# AP_board.net
KiCad netlist of a schematic drawn in EAGLE
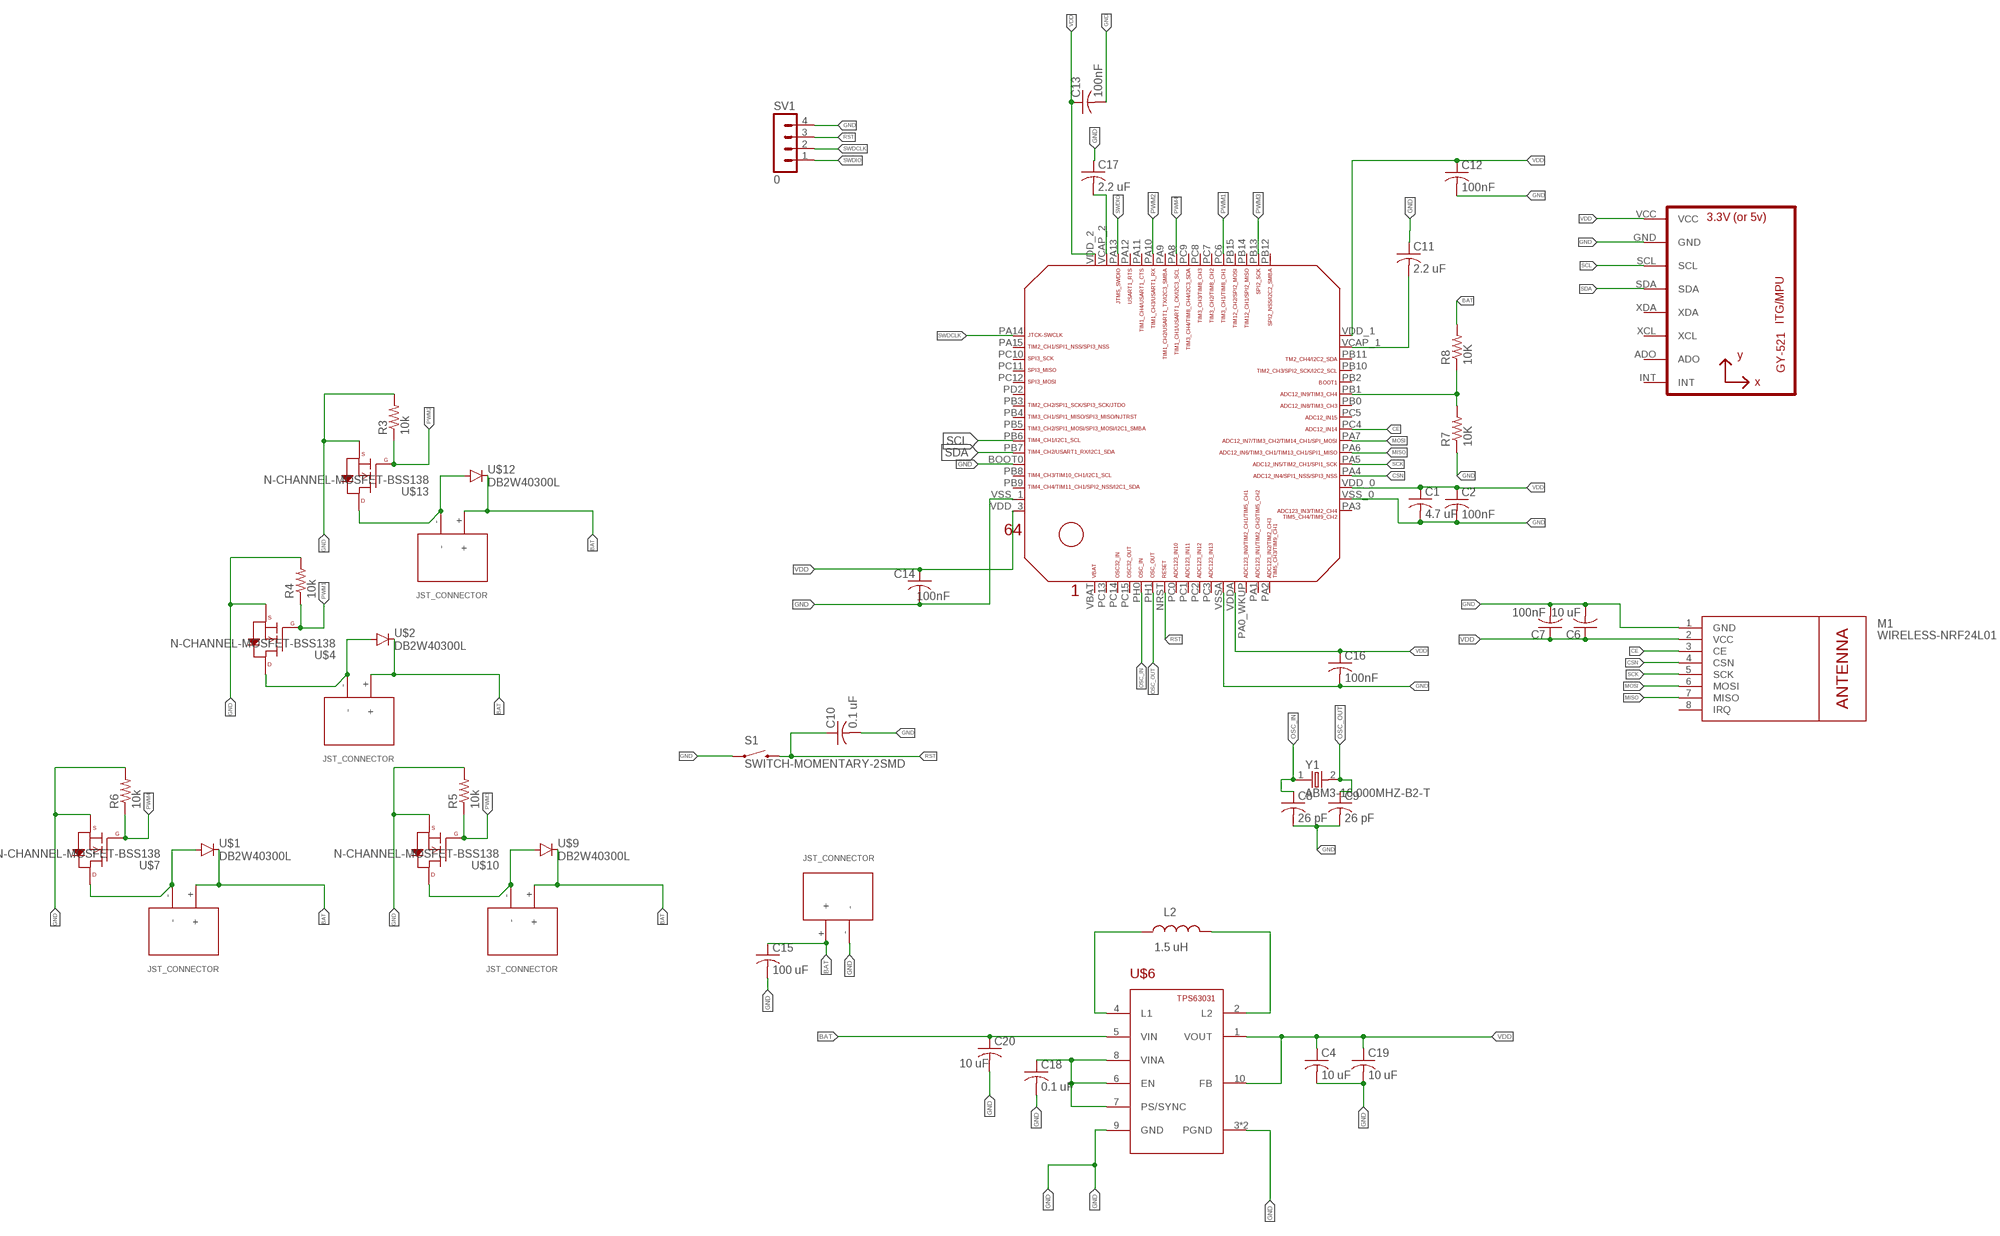
[diagram p0: schematic, sheet 1]

(export (version "E")
  (design (tool "Eeschema 10.0.6"))
  (components
    (comp (ref "C1")
      (value "4.7 uF")
      (footprint "eagle-import:C0603")
      (libsource (lib "eagle-import") (part "C-USC0603"))
    )
    (comp (ref "C2")
      (value "100nF")
      (footprint "eagle-import:C0603")
      (libsource (lib "eagle-import") (part "C-USC0603"))
    )
    (comp (ref "C4")
      (value "10 uF")
      (footprint "eagle-import:C0603")
      (libsource (lib "eagle-import") (part "C-USC0603"))
    )
    (comp (ref "C6")
      (value "10 uF")
      (footprint "eagle-import:C0603")
      (libsource (lib "eagle-import") (part "C-USC0603"))
    )
    (comp (ref "C7")
      (value "100nF")
      (footprint "eagle-import:C0603")
      (libsource (lib "eagle-import") (part "C-USC0603"))
    )
    (comp (ref "C8")
      (value "26 pF")
      (footprint "eagle-import:C0603")
      (libsource (lib "eagle-import") (part "C-USC0603"))
    )
    (comp (ref "C9")
      (value "26 pF")
      (footprint "eagle-import:C0603")
      (libsource (lib "eagle-import") (part "C-USC0603"))
    )
    (comp (ref "C10")
      (value "0.1 uF")
      (footprint "eagle-import:C0603")
      (libsource (lib "eagle-import") (part "C-USC0603"))
    )
    (comp (ref "C11")
      (value "2.2 uF")
      (footprint "eagle-import:C0603")
      (libsource (lib "eagle-import") (part "C-USC0603"))
    )
    (comp (ref "C12")
      (value "100nF")
      (footprint "eagle-import:C0603")
      (libsource (lib "eagle-import") (part "C-USC0603"))
    )
    (comp (ref "C13")
      (value "100nF")
      (footprint "eagle-import:C0603")
      (libsource (lib "eagle-import") (part "C-USC0603"))
    )
    (comp (ref "C14")
      (value "100nF")
      (footprint "eagle-import:C0603")
      (libsource (lib "eagle-import") (part "C-USC0603"))
    )
    (comp (ref "C15")
      (value "100 uF")
      (footprint "eagle-import:C1206")
      (libsource (lib "eagle-import") (part "C-USC1206"))
    )
    (comp (ref "C16")
      (value "100nF")
      (footprint "eagle-import:C0603")
      (libsource (lib "eagle-import") (part "C-USC0603"))
    )
    (comp (ref "C17")
      (value "2.2 uF")
      (footprint "eagle-import:C0603")
      (libsource (lib "eagle-import") (part "C-USC0603"))
    )
    (comp (ref "C18")
      (value "0.1 uF")
      (footprint "eagle-import:C0603")
      (libsource (lib "eagle-import") (part "C-USC0603"))
    )
    (comp (ref "C19")
      (value "10 uF")
      (footprint "eagle-import:C0603")
      (libsource (lib "eagle-import") (part "C-USC0603"))
    )
    (comp (ref "C20")
      (value "10 uF")
      (footprint "eagle-import:C0603")
      (libsource (lib "eagle-import") (part "C-USC0603"))
    )
    (comp (ref "L2")
      (value "1.5 uH")
      (footprint "eagle-import:IND1212")
      (libsource (lib "eagle-import") (part "INDUCTOR"))
    )
    (comp (ref "M1")
      (value "WIRELESS-NRF24L01")
      (footprint "eagle-import:WIRELESS-NRF24L01")
      (libsource (lib "eagle-import") (part "WIRELESS-NRF24L01"))
    )
    (comp (ref "R3")
      (value "10k")
      (footprint "eagle-import:R0603")
      (libsource (lib "eagle-import") (part "R-US_R0603"))
    )
    (comp (ref "R4")
      (value "10k")
      (footprint "eagle-import:R0603")
      (libsource (lib "eagle-import") (part "R-US_R0603"))
    )
    (comp (ref "R5")
      (value "10k")
      (footprint "eagle-import:R0603")
      (libsource (lib "eagle-import") (part "R-US_R0603"))
    )
    (comp (ref "R6")
      (value "10k")
      (footprint "eagle-import:R0603")
      (libsource (lib "eagle-import") (part "R-US_R0603"))
    )
    (comp (ref "R7")
      (value "10K")
      (footprint "eagle-import:R0603")
      (libsource (lib "eagle-import") (part "R-US_R0603"))
    )
    (comp (ref "R8")
      (value "10K")
      (footprint "eagle-import:R0603")
      (libsource (lib "eagle-import") (part "R-US_R0603"))
    )
    (comp (ref "S1")
      (value "SWITCH-MOMENTARY-2SMD")
      (footprint "eagle-import:TACTILE-SWITCH-SMD")
      (libsource (lib "eagle-import") (part "SWITCH-MOMENTARY-2SMD"))
    )
    (comp (ref "SV1")
      (value "0")
      (footprint "eagle-import:MA04-1")
      (libsource (lib "eagle-import") (part "MA04-1"))
    )
    (comp (ref "U$1")
      (value "DB2W40300L")
      (footprint "eagle-import:MINI2-F3-B")
      (libsource (lib "eagle-import") (part "DB2W40300L"))
    )
    (comp (ref "U$2")
      (value "DB2W40300L")
      (footprint "eagle-import:MINI2-F3-B")
      (libsource (lib "eagle-import") (part "DB2W40300L"))
    )
    (comp (ref "U$3")
      (value "STM32F405/415_LQFP64")
      (footprint "eagle-import:STM32F405_415_LQFP64")
      (libsource (lib "eagle-import") (part "STM32F405/415_LQFP64"))
    )
    (comp (ref "U$4")
      (value "N-CHANNEL-MOSFET-BSS138")
      (footprint "eagle-import:SOT23-3")
      (libsource (lib "eagle-import") (part "N-CHANNEL-MOSFET-BSS138"))
    )
    (comp (ref "U$5")
      (value "JST_CONNECTOR_FEMALE")
      (footprint "eagle-import:JST_CONNECTOR_FEMALE")
      (libsource (lib "eagle-import") (part "JST_CONNECTOR_FEMALE"))
    )
    (comp (ref "U$6")
      (value "TPS63031")
      (footprint "eagle-import:SON-10")
      (libsource (lib "eagle-import") (part "TPS63031"))
    )
    (comp (ref "U$7")
      (value "N-CHANNEL-MOSFET-BSS138")
      (footprint "eagle-import:SOT23-3")
      (libsource (lib "eagle-import") (part "N-CHANNEL-MOSFET-BSS138"))
    )
    (comp (ref "U$8")
      (value "JST_CONNECTOR_FEMALE")
      (footprint "eagle-import:JST_CONNECTOR_FEMALE")
      (libsource (lib "eagle-import") (part "JST_CONNECTOR_FEMALE"))
    )
    (comp (ref "U$9")
      (value "DB2W40300L")
      (footprint "eagle-import:MINI2-F3-B")
      (libsource (lib "eagle-import") (part "DB2W40300L"))
    )
    (comp (ref "U$10")
      (value "N-CHANNEL-MOSFET-BSS138")
      (footprint "eagle-import:SOT23-3")
      (libsource (lib "eagle-import") (part "N-CHANNEL-MOSFET-BSS138"))
    )
    (comp (ref "U$11")
      (value "JST_CONNECTOR_FEMALE")
      (footprint "eagle-import:JST_CONNECTOR_FEMALE")
      (libsource (lib "eagle-import") (part "JST_CONNECTOR_FEMALE"))
    )
    (comp (ref "U$12")
      (value "DB2W40300L")
      (footprint "eagle-import:MINI2-F3-B")
      (libsource (lib "eagle-import") (part "DB2W40300L"))
    )
    (comp (ref "U$13")
      (value "N-CHANNEL-MOSFET-BSS138")
      (footprint "eagle-import:SOT23-3")
      (libsource (lib "eagle-import") (part "N-CHANNEL-MOSFET-BSS138"))
    )
    (comp (ref "U$14")
      (value "JST_CONNECTOR_FEMALE")
      (footprint "eagle-import:JST_CONNECTOR_FEMALE")
      (libsource (lib "eagle-import") (part "JST_CONNECTOR_FEMALE"))
    )
    (comp (ref "U$17")
      (value "JST_CONNECTOR_FEMALE")
      (footprint "eagle-import:JST_CONNECTOR_FEMALE")
      (libsource (lib "eagle-import") (part "JST_CONNECTOR_FEMALE"))
    )
    (comp (ref "U1")
      (value "GY-521MPU6050")
      (footprint "eagle-import:GY-521")
      (libsource (lib "eagle-import") (part "GY-521MPU6050"))
    )
    (comp (ref "Y1")
      (value "ABM3-16.000MHZ-B2-T")
      (footprint "eagle-import:XTAL500X320X130N")
      (fields (field (name "DIGI-KEY_PART_NUMBER") "535-9103-1-ND") (field (name "MF") "Abracon"))
      (libsource (lib "eagle-import") (part "ABM3-16.000MHZ-B2-T"))
    )
  )
  (nets
    (net (code "1") (name "BAT") (class "Default")
      (node (ref "C15") (pin "1") (pinfunction "1_1") (pintype "passive"))
      (node (ref "C20") (pin "1") (pinfunction "1_1") (pintype "passive"))
      (node (ref "R8") (pin "2") (pinfunction "2_2") (pintype "passive"))
      (node (ref "U$1") (pin "NEG") (pinfunction "GPIN_NEG") (pintype "passive"))
      (node (ref "U$11") (pin "+") (pinfunction "+_+") (pintype "bidirectional"))
      (node (ref "U$12") (pin "NEG") (pinfunction "GPIN_NEG") (pintype "passive"))
      (node (ref "U$14") (pin "+") (pinfunction "+_+") (pintype "bidirectional"))
      (node (ref "U$17") (pin "+") (pinfunction "+_+") (pintype "bidirectional"))
      (node (ref "U$2") (pin "NEG") (pinfunction "GPIN_NEG") (pintype "passive"))
      (node (ref "U$5") (pin "+") (pinfunction "+_+") (pintype "bidirectional"))
      (node (ref "U$6") (pin "5") (pinfunction "VIN_5") (pintype "bidirectional"))
      (node (ref "U$8") (pin "+") (pinfunction "+_+") (pintype "bidirectional"))
      (node (ref "U$9") (pin "NEG") (pinfunction "GPIN_NEG") (pintype "passive"))
    )
    (net (code "2") (name "CE") (class "Default")
      (node (ref "M1") (pin "3") (pinfunction "CE_3") (pintype "bidirectional"))
      (node (ref "U$3") (pin "PC4") (pinfunction "PC4_PC4") (pintype "bidirectional"))
    )
    (net (code "3") (name "CSN") (class "Default")
      (node (ref "M1") (pin "4") (pinfunction "CSN_4") (pintype "bidirectional"))
      (node (ref "U$3") (pin "PA4") (pinfunction "PA4_PA4") (pintype "bidirectional"))
    )
    (net (code "4") (name "GND") (class "Default")
      (node (ref "C1") (pin "2") (pinfunction "2_2") (pintype "passive"))
      (node (ref "C10") (pin "2") (pinfunction "2_2") (pintype "passive"))
      (node (ref "C11") (pin "1") (pinfunction "1_1") (pintype "passive"))
      (node (ref "C12") (pin "2") (pinfunction "2_2") (pintype "passive"))
      (node (ref "C13") (pin "2") (pinfunction "2_2") (pintype "passive"))
      (node (ref "C14") (pin "2") (pinfunction "2_2") (pintype "passive"))
      (node (ref "C15") (pin "2") (pinfunction "2_2") (pintype "passive"))
      (node (ref "C16") (pin "2") (pinfunction "2_2") (pintype "passive"))
      (node (ref "C17") (pin "1") (pinfunction "1_1") (pintype "passive"))
      (node (ref "C18") (pin "2") (pinfunction "2_2") (pintype "passive"))
      (node (ref "C19") (pin "2") (pinfunction "2_2") (pintype "passive"))
      (node (ref "C2") (pin "2") (pinfunction "2_2") (pintype "passive"))
      (node (ref "C20") (pin "2") (pinfunction "2_2") (pintype "passive"))
      (node (ref "C4") (pin "2") (pinfunction "2_2") (pintype "passive"))
      (node (ref "C6") (pin "2") (pinfunction "2_2") (pintype "passive"))
      (node (ref "C7") (pin "2") (pinfunction "2_2") (pintype "passive"))
      (node (ref "C8") (pin "2") (pinfunction "2_2") (pintype "passive"))
      (node (ref "C9") (pin "2") (pinfunction "2_2") (pintype "passive"))
      (node (ref "M1") (pin "1") (pinfunction "GND_1") (pintype "power_in"))
      (node (ref "R3") (pin "2") (pinfunction "2_2") (pintype "passive"))
      (node (ref "R4") (pin "2") (pinfunction "2_2") (pintype "passive"))
      (node (ref "R5") (pin "2") (pinfunction "2_2") (pintype "passive"))
      (node (ref "R6") (pin "2") (pinfunction "2_2") (pintype "passive"))
      (node (ref "R7") (pin "1") (pinfunction "1_1") (pintype "passive"))
      (node (ref "S1") (pin "1") (pinfunction "1_1") (pintype "passive"))
      (node (ref "SV1") (pin "4") (pinfunction "4_4") (pintype "passive"))
      (node (ref "U$10") (pin "2") (pinfunction "S_2") (pintype "passive"))
      (node (ref "U$13") (pin "2") (pinfunction "S_2") (pintype "passive"))
      (node (ref "U$17") (pin "-") (pinfunction "-_-") (pintype "bidirectional"))
      (node (ref "U$3") (pin "BOOT0") (pinfunction "BOOT0_BOOT0") (pintype "bidirectional"))
      (node (ref "U$3") (pin "VSSA") (pinfunction "VSSA_VSSA") (pintype "bidirectional"))
      (node (ref "U$3") (pin "VSS_0") (pinfunction "VSS_0_VSS_0") (pintype "bidirectional"))
      (node (ref "U$3") (pin "VSS_1") (pinfunction "VSS_1_VSS_1") (pintype "bidirectional"))
      (node (ref "U$4") (pin "2") (pinfunction "S_2") (pintype "passive"))
      (node (ref "U$6") (pin "3") (pinfunction "PGND_3") (pintype "bidirectional"))
      (node (ref "U$6") (pin "9") (pinfunction "GND_9") (pintype "bidirectional"))
      (node (ref "U$6") (pin "PAD") (pinfunction "PGND_PAD") (pintype "bidirectional"))
      (node (ref "U$7") (pin "2") (pinfunction "S_2") (pintype "passive"))
      (node (ref "U1") (pin "GND") (pinfunction "GND_GND") (pintype "bidirectional"))
    )
    (net (code "5") (name "MISO") (class "Default")
      (node (ref "M1") (pin "7") (pinfunction "MISO_7") (pintype "bidirectional"))
      (node (ref "U$3") (pin "PA6") (pinfunction "PA6_PA6") (pintype "bidirectional"))
    )
    (net (code "6") (name "MOSI") (class "Default")
      (node (ref "M1") (pin "6") (pinfunction "MOSI_6") (pintype "bidirectional"))
      (node (ref "U$3") (pin "PA7") (pinfunction "PA7_PA7") (pintype "bidirectional"))
    )
    (net (code "7") (name "Net-(C11-Pad2)") (class "Default")
      (node (ref "C11") (pin "2") (pinfunction "2_2") (pintype "passive"))
      (node (ref "U$3") (pin "VCAP_1") (pinfunction "VCAP_1_VCAP_1") (pintype "bidirectional"))
    )
    (net (code "8") (name "Net-(C17-Pad2)") (class "Default")
      (node (ref "C17") (pin "2") (pinfunction "2_2") (pintype "passive"))
      (node (ref "U$3") (pin "VCAP_2") (pinfunction "VCAP_2_VCAP_2") (pintype "bidirectional"))
    )
    (net (code "9") (name "Net-(L2-1)") (class "Default")
      (node (ref "L2") (pin "P$1") (pinfunction "1_P$1") (pintype "passive"))
      (node (ref "U$6") (pin "4") (pinfunction "L1_4") (pintype "bidirectional"))
    )
    (net (code "10") (name "Net-(L2-2)") (class "Default")
      (node (ref "L2") (pin "P$2") (pinfunction "2_P$2") (pintype "passive"))
      (node (ref "U$6") (pin "2") (pinfunction "L2_2") (pintype "bidirectional"))
    )
    (net (code "11") (name "Net-(R7-Pad2)") (class "Default")
      (node (ref "R7") (pin "2") (pinfunction "2_2") (pintype "passive"))
      (node (ref "R8") (pin "1") (pinfunction "1_1") (pintype "passive"))
      (node (ref "U$3") (pin "PB1") (pinfunction "PB1_PB1") (pintype "bidirectional"))
    )
    (net (code "12") (name "Net-(U$1-PPIN)") (class "Default")
      (node (ref "U$1") (pin "POS") (pinfunction "PPIN_POS") (pintype "passive"))
      (node (ref "U$7") (pin "3") (pinfunction "D_3") (pintype "passive"))
      (node (ref "U$8") (pin "-") (pinfunction "-_-") (pintype "bidirectional"))
    )
    (net (code "13") (name "Net-(U$2-PPIN)") (class "Default")
      (node (ref "U$2") (pin "POS") (pinfunction "PPIN_POS") (pintype "passive"))
      (node (ref "U$4") (pin "3") (pinfunction "D_3") (pintype "passive"))
      (node (ref "U$5") (pin "-") (pinfunction "-_-") (pintype "bidirectional"))
    )
    (net (code "14") (name "Net-(U$6-EN)") (class "Default")
      (node (ref "C18") (pin "1") (pinfunction "1_1") (pintype "passive"))
      (node (ref "U$6") (pin "6") (pinfunction "EN_6") (pintype "bidirectional"))
      (node (ref "U$6") (pin "7") (pinfunction "PS/SYNC_7") (pintype "bidirectional"))
      (node (ref "U$6") (pin "8") (pinfunction "VINA_8") (pintype "bidirectional"))
    )
    (net (code "15") (name "Net-(U$10-D)") (class "Default")
      (node (ref "U$10") (pin "3") (pinfunction "D_3") (pintype "passive"))
      (node (ref "U$11") (pin "-") (pinfunction "-_-") (pintype "bidirectional"))
      (node (ref "U$9") (pin "POS") (pinfunction "PPIN_POS") (pintype "passive"))
    )
    (net (code "16") (name "Net-(U$12-PPIN)") (class "Default")
      (node (ref "U$12") (pin "POS") (pinfunction "PPIN_POS") (pintype "passive"))
      (node (ref "U$13") (pin "3") (pinfunction "D_3") (pintype "passive"))
      (node (ref "U$14") (pin "-") (pinfunction "-_-") (pintype "bidirectional"))
    )
    (net (code "17") (name "OSC_IN") (class "Default")
      (node (ref "C8") (pin "1") (pinfunction "1_1") (pintype "passive"))
      (node (ref "U$3") (pin "PH0") (pinfunction "PH0_PH0") (pintype "bidirectional"))
      (node (ref "Y1") (pin "1") (pinfunction "1_1") (pintype "passive"))
    )
    (net (code "18") (name "OSC_OUT") (class "Default")
      (node (ref "C9") (pin "1") (pinfunction "1_1") (pintype "passive"))
      (node (ref "U$3") (pin "PH1") (pinfunction "PH1_PH1") (pintype "bidirectional"))
      (node (ref "Y1") (pin "2") (pinfunction "2_2") (pintype "passive"))
    )
    (net (code "19") (name "PWM1") (class "Default")
      (node (ref "R4") (pin "1") (pinfunction "1_1") (pintype "passive"))
      (node (ref "U$3") (pin "PC6") (pinfunction "PC6_PC6") (pintype "bidirectional"))
      (node (ref "U$4") (pin "1") (pinfunction "G_1") (pintype "passive"))
    )
    (net (code "20") (name "PWM2") (class "Default")
      (node (ref "R3") (pin "1") (pinfunction "1_1") (pintype "passive"))
      (node (ref "U$13") (pin "1") (pinfunction "G_1") (pintype "passive"))
      (node (ref "U$3") (pin "PA10") (pinfunction "PA10_PA10") (pintype "bidirectional"))
    )
    (net (code "21") (name "PWM3") (class "Default")
      (node (ref "R5") (pin "1") (pinfunction "1_1") (pintype "passive"))
      (node (ref "U$10") (pin "1") (pinfunction "G_1") (pintype "passive"))
      (node (ref "U$3") (pin "PB13") (pinfunction "PB13_PB13") (pintype "bidirectional"))
    )
    (net (code "22") (name "PWM4") (class "Default")
      (node (ref "R6") (pin "1") (pinfunction "1_1") (pintype "passive"))
      (node (ref "U$3") (pin "PA8") (pinfunction "PA8_PA8") (pintype "bidirectional"))
      (node (ref "U$7") (pin "1") (pinfunction "G_1") (pintype "passive"))
    )
    (net (code "23") (name "RST") (class "Default")
      (node (ref "C10") (pin "1") (pinfunction "1_1") (pintype "passive"))
      (node (ref "S1") (pin "3") (pinfunction "2_3") (pintype "passive"))
      (node (ref "SV1") (pin "3") (pinfunction "3_3") (pintype "passive"))
      (node (ref "U$3") (pin "NRST") (pinfunction "NRST_NRST") (pintype "bidirectional"))
    )
    (net (code "24") (name "SCK") (class "Default")
      (node (ref "M1") (pin "5") (pinfunction "SCK_5") (pintype "bidirectional"))
      (node (ref "U$3") (pin "PA5") (pinfunction "PA5_PA5") (pintype "bidirectional"))
    )
    (net (code "25") (name "SCL") (class "Default")
      (node (ref "U$3") (pin "PB6") (pinfunction "PB6_PB6") (pintype "bidirectional"))
      (node (ref "U1") (pin "SCL") (pinfunction "SCL_SCL") (pintype "bidirectional"))
    )
    (net (code "26") (name "SDA") (class "Default")
      (node (ref "U$3") (pin "PB7") (pinfunction "PB7_PB7") (pintype "bidirectional"))
      (node (ref "U1") (pin "SDA") (pinfunction "SDA_SDA") (pintype "bidirectional"))
    )
    (net (code "27") (name "SWDCLK") (class "Default")
      (node (ref "SV1") (pin "2") (pinfunction "2_2") (pintype "passive"))
      (node (ref "U$3") (pin "PA14") (pinfunction "PA14_PA14") (pintype "bidirectional"))
    )
    (net (code "28") (name "SWDIO") (class "Default")
      (node (ref "SV1") (pin "1") (pinfunction "1_1") (pintype "passive"))
      (node (ref "U$3") (pin "PA13") (pinfunction "PA13_PA13") (pintype "bidirectional"))
    )
    (net (code "29") (name "VDD") (class "Default")
      (node (ref "C1") (pin "1") (pinfunction "1_1") (pintype "passive"))
      (node (ref "C12") (pin "1") (pinfunction "1_1") (pintype "passive"))
      (node (ref "C13") (pin "1") (pinfunction "1_1") (pintype "passive"))
      (node (ref "C14") (pin "1") (pinfunction "1_1") (pintype "passive"))
      (node (ref "C16") (pin "1") (pinfunction "1_1") (pintype "passive"))
      (node (ref "C19") (pin "1") (pinfunction "1_1") (pintype "passive"))
      (node (ref "C2") (pin "1") (pinfunction "1_1") (pintype "passive"))
      (node (ref "C4") (pin "1") (pinfunction "1_1") (pintype "passive"))
      (node (ref "C6") (pin "1") (pinfunction "1_1") (pintype "passive"))
      (node (ref "C7") (pin "1") (pinfunction "1_1") (pintype "passive"))
      (node (ref "M1") (pin "2") (pinfunction "VCC_2") (pintype "power_in"))
      (node (ref "U$3") (pin "VDDA") (pinfunction "VDDA_VDDA") (pintype "bidirectional"))
      (node (ref "U$3") (pin "VDD_0") (pinfunction "VDD_0_VDD_0") (pintype "bidirectional"))
      (node (ref "U$3") (pin "VDD_1") (pinfunction "VDD_1_VDD_1") (pintype "bidirectional"))
      (node (ref "U$3") (pin "VDD_2") (pinfunction "VDD_2_VDD_2") (pintype "bidirectional"))
      (node (ref "U$3") (pin "VDD_3") (pinfunction "VDD_3_VDD_3") (pintype "bidirectional"))
      (node (ref "U$6") (pin "1") (pinfunction "VOUT_1") (pintype "bidirectional"))
      (node (ref "U$6") (pin "10") (pinfunction "FB_10") (pintype "bidirectional"))
      (node (ref "U1") (pin "VCC") (pinfunction "VCC_VCC") (pintype "bidirectional"))
    )
    (net (code "30") (name "unconnected-(M1-IRQ-Pad8)") (class "Default")
      (node (ref "M1") (pin "8") (pinfunction "IRQ_8") (pintype "bidirectional"))
    )
    (net (code "31") (name "unconnected-(U$3-PA0_AKUP-PadPA0_WKUP)") (class "Default")
      (node (ref "U$3") (pin "PA0_WKUP") (pinfunction "PA0_AKUP_PA0_WKUP") (pintype "bidirectional"))
    )
    (net (code "32") (name "unconnected-(U$3-PadPA1)") (class "Default")
      (node (ref "U$3") (pin "PA1") (pinfunction "PA1_PA1") (pintype "bidirectional"))
    )
    (net (code "33") (name "unconnected-(U$3-PadPA2)") (class "Default")
      (node (ref "U$3") (pin "PA2") (pinfunction "PA2_PA2") (pintype "bidirectional"))
    )
    (net (code "34") (name "unconnected-(U$3-PadPA3)") (class "Default")
      (node (ref "U$3") (pin "PA3") (pinfunction "PA3_PA3") (pintype "bidirectional"))
    )
    (net (code "35") (name "unconnected-(U$3-PadPA9)") (class "Default")
      (node (ref "U$3") (pin "PA9") (pinfunction "PA9_PA9") (pintype "bidirectional"))
    )
    (net (code "36") (name "unconnected-(U$3-PadPA11)") (class "Default")
      (node (ref "U$3") (pin "PA11") (pinfunction "PA11_PA11") (pintype "bidirectional"))
    )
    (net (code "37") (name "unconnected-(U$3-PadPA12)") (class "Default")
      (node (ref "U$3") (pin "PA12") (pinfunction "PA12_PA12") (pintype "bidirectional"))
    )
    (net (code "38") (name "unconnected-(U$3-PadPA15)") (class "Default")
      (node (ref "U$3") (pin "PA15") (pinfunction "PA15_PA15") (pintype "bidirectional"))
    )
    (net (code "39") (name "unconnected-(U$3-PadPB0)") (class "Default")
      (node (ref "U$3") (pin "PB0") (pinfunction "PB0_PB0") (pintype "bidirectional"))
    )
    (net (code "40") (name "unconnected-(U$3-PadPB2)") (class "Default")
      (node (ref "U$3") (pin "PB2") (pinfunction "PB2_PB2") (pintype "bidirectional"))
    )
    (net (code "41") (name "unconnected-(U$3-PadPB3)") (class "Default")
      (node (ref "U$3") (pin "PB3") (pinfunction "PB3_PB3") (pintype "bidirectional"))
    )
    (net (code "42") (name "unconnected-(U$3-PadPB4)") (class "Default")
      (node (ref "U$3") (pin "PB4") (pinfunction "PB4_PB4") (pintype "bidirectional"))
    )
    (net (code "43") (name "unconnected-(U$3-PadPB5)") (class "Default")
      (node (ref "U$3") (pin "PB5") (pinfunction "PB5_PB5") (pintype "bidirectional"))
    )
    (net (code "44") (name "unconnected-(U$3-PadPB8)") (class "Default")
      (node (ref "U$3") (pin "PB8") (pinfunction "PB8_PB8") (pintype "bidirectional"))
    )
    (net (code "45") (name "unconnected-(U$3-PadPB9)") (class "Default")
      (node (ref "U$3") (pin "PB9") (pinfunction "PB9_PB9") (pintype "bidirectional"))
    )
    (net (code "46") (name "unconnected-(U$3-PadPB10)") (class "Default")
      (node (ref "U$3") (pin "PB10") (pinfunction "PB10_PB10") (pintype "bidirectional"))
    )
    (net (code "47") (name "unconnected-(U$3-PadPB11)") (class "Default")
      (node (ref "U$3") (pin "PB11") (pinfunction "PB11_PB11") (pintype "bidirectional"))
    )
    (net (code "48") (name "unconnected-(U$3-PadPB12)") (class "Default")
      (node (ref "U$3") (pin "PB12") (pinfunction "PB12_PB12") (pintype "bidirectional"))
    )
    (net (code "49") (name "unconnected-(U$3-PadPB14)") (class "Default")
      (node (ref "U$3") (pin "PB14") (pinfunction "PB14_PB14") (pintype "bidirectional"))
    )
    (net (code "50") (name "unconnected-(U$3-PadPB15)") (class "Default")
      (node (ref "U$3") (pin "PB15") (pinfunction "PB15_PB15") (pintype "bidirectional"))
    )
    (net (code "51") (name "unconnected-(U$3-PadPC0)") (class "Default")
      (node (ref "U$3") (pin "PC0") (pinfunction "PC0_PC0") (pintype "bidirectional"))
    )
    (net (code "52") (name "unconnected-(U$3-PadPC1)") (class "Default")
      (node (ref "U$3") (pin "PC1") (pinfunction "PC1_PC1") (pintype "bidirectional"))
    )
    (net (code "53") (name "unconnected-(U$3-PadPC2)") (class "Default")
      (node (ref "U$3") (pin "PC2") (pinfunction "PC2_PC2") (pintype "bidirectional"))
    )
    (net (code "54") (name "unconnected-(U$3-PadPC3)") (class "Default")
      (node (ref "U$3") (pin "PC3") (pinfunction "PC3_PC3") (pintype "bidirectional"))
    )
    (net (code "55") (name "unconnected-(U$3-PadPC5)") (class "Default")
      (node (ref "U$3") (pin "PC5") (pinfunction "PC5_PC5") (pintype "bidirectional"))
    )
    (net (code "56") (name "unconnected-(U$3-PadPC7)") (class "Default")
      (node (ref "U$3") (pin "PC7") (pinfunction "PC7_PC7") (pintype "bidirectional"))
    )
    (net (code "57") (name "unconnected-(U$3-PadPC8)") (class "Default")
      (node (ref "U$3") (pin "PC8") (pinfunction "PC8_PC8") (pintype "bidirectional"))
    )
    (net (code "58") (name "unconnected-(U$3-PadPC9)") (class "Default")
      (node (ref "U$3") (pin "PC9") (pinfunction "PC9_PC9") (pintype "bidirectional"))
    )
    (net (code "59") (name "unconnected-(U$3-PadPC10)") (class "Default")
      (node (ref "U$3") (pin "PC10") (pinfunction "PC10_PC10") (pintype "bidirectional"))
    )
    (net (code "60") (name "unconnected-(U$3-PadPC11)") (class "Default")
      (node (ref "U$3") (pin "PC11") (pinfunction "PC11_PC11") (pintype "bidirectional"))
    )
    (net (code "61") (name "unconnected-(U$3-PadPC12)") (class "Default")
      (node (ref "U$3") (pin "PC12") (pinfunction "PC12_PC12") (pintype "bidirectional"))
    )
    (net (code "62") (name "unconnected-(U$3-PadPC13)") (class "Default")
      (node (ref "U$3") (pin "PC13") (pinfunction "PC13_PC13") (pintype "bidirectional"))
    )
    (net (code "63") (name "unconnected-(U$3-PadPC14)") (class "Default")
      (node (ref "U$3") (pin "PC14") (pinfunction "PC14_PC14") (pintype "bidirectional"))
    )
    (net (code "64") (name "unconnected-(U$3-PadPC15)") (class "Default")
      (node (ref "U$3") (pin "PC15") (pinfunction "PC15_PC15") (pintype "bidirectional"))
    )
    (net (code "65") (name "unconnected-(U$3-PadPD2)") (class "Default")
      (node (ref "U$3") (pin "PD2") (pinfunction "PD2_PD2") (pintype "bidirectional"))
    )
    (net (code "66") (name "unconnected-(U$3-PadVBAT)") (class "Default")
      (node (ref "U$3") (pin "VBAT") (pinfunction "VBAT_VBAT") (pintype "bidirectional"))
    )
    (net (code "67") (name "unconnected-(U1-PadADO)") (class "Default")
      (node (ref "U1") (pin "ADO") (pinfunction "ADO_ADO") (pintype "bidirectional"))
    )
    (net (code "68") (name "unconnected-(U1-PadINT)") (class "Default")
      (node (ref "U1") (pin "INT") (pinfunction "INT_INT") (pintype "bidirectional"))
    )
    (net (code "69") (name "unconnected-(U1-PadXCL)") (class "Default")
      (node (ref "U1") (pin "XCL") (pinfunction "XCL_XCL") (pintype "bidirectional"))
    )
    (net (code "70") (name "unconnected-(U1-PadXDA)") (class "Default")
      (node (ref "U1") (pin "XDA") (pinfunction "XDA_XDA") (pintype "bidirectional"))
    )
  )
)
